# HDMI-OUT.net
KiCad netlist of a schematic drawn in Altium Designer
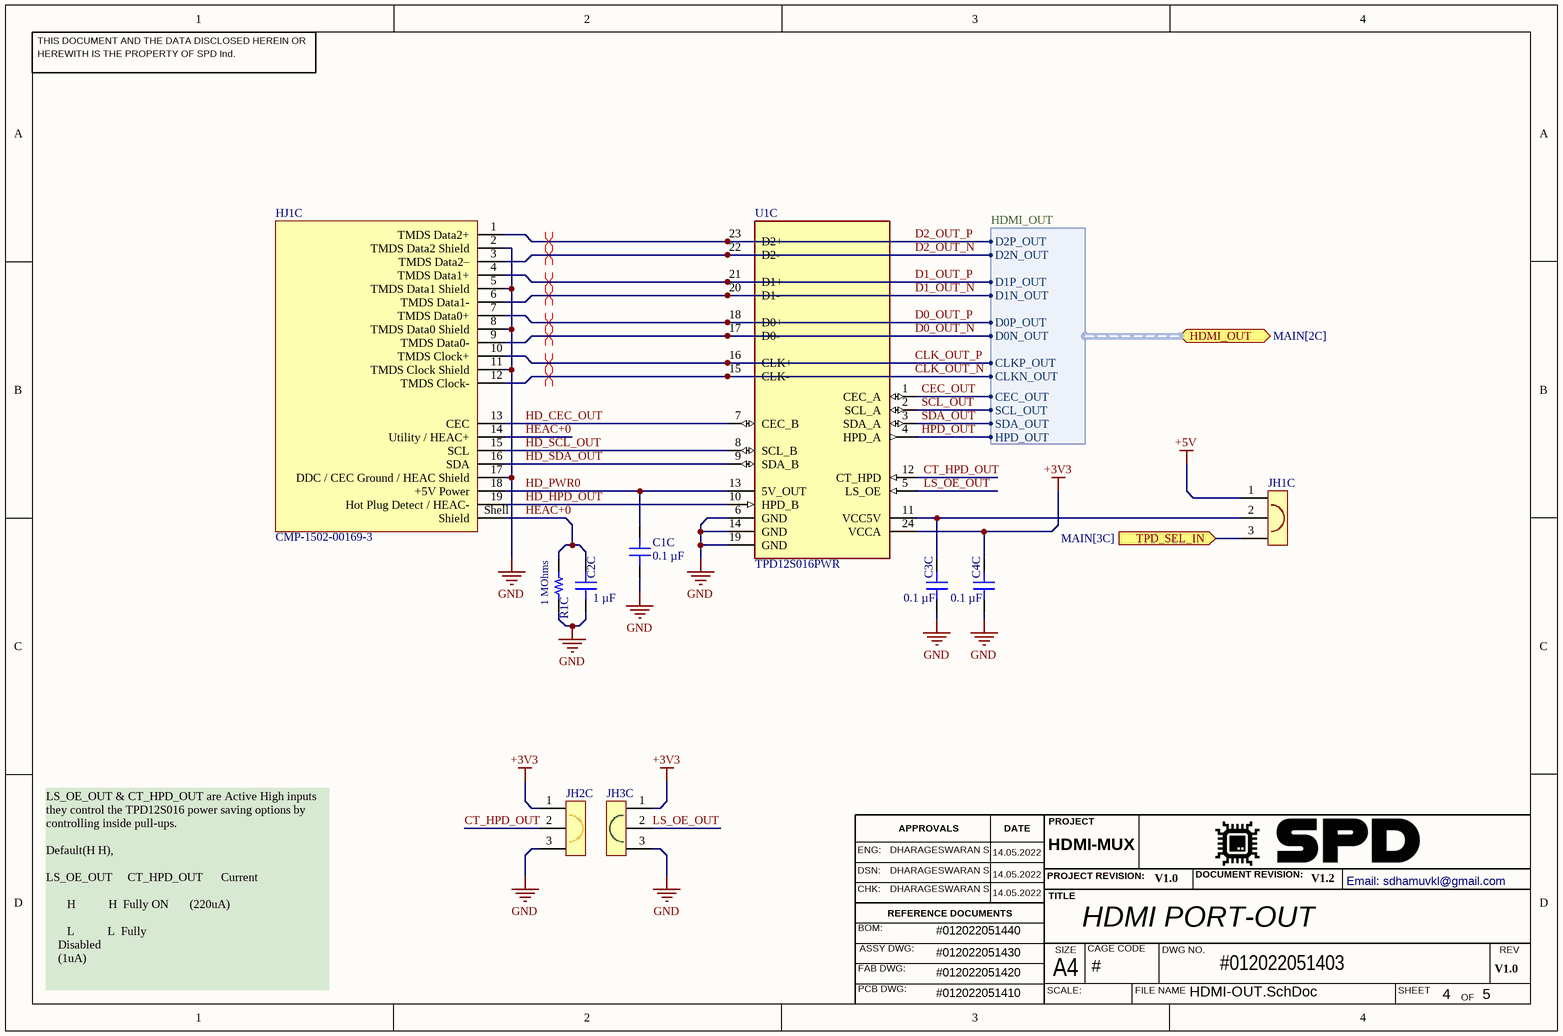
[diagram p0: HDMI-OUT.SchDoc]

(export (version "E")
  (design (tool "Eeschema 10.0.6"))
  (components
    (comp (ref "C1C")
      (value "0.1 µF")
      (footprint "CAP 0603_1608")
      (description "CAP CER 0.1UF 10V X7R 0603")
      (fields (field (name "PART NUMBER") "CC0603KRX7R6BB104") (field (name "MANUFACTURER") "Yageo"))
      (libsource (lib "Postgres Altium Library - altium_library") (part "Capacitor"))
    )
    (comp (ref "C2C")
      (value "1 µF")
      (footprint "CAP 0603_1608")
      (description "CAP CER 1UF 10V Y5V 0603")
      (fields (field (name "PART NUMBER") "CC0603ZRY5V6BB105") (field (name "MANUFACTURER") "Yageo"))
      (libsource (lib "Postgres Altium Library - altium_library") (part "Capacitor"))
    )
    (comp (ref "C3C")
      (value "0.1 µF")
      (footprint "CAP 0603_1608")
      (description "CAP CER 0.1UF 10V X7R 0603")
      (fields (field (name "PART NUMBER") "CC0603KRX7R6BB104") (field (name "MANUFACTURER") "Yageo"))
      (libsource (lib "Postgres Altium Library - altium_library") (part "Capacitor"))
    )
    (comp (ref "C4C")
      (value "0.1 µF")
      (footprint "CAP 0603_1608")
      (description "CAP CER 0.1UF 10V X7R 0603")
      (fields (field (name "PART NUMBER") "CC0603KRX7R6BB104") (field (name "MANUFACTURER") "Yageo"))
      (libsource (lib "Postgres Altium Library - altium_library") (part "Capacitor"))
    )
    (comp (ref "HJ1C")
      (value "CMP-1502-00169-3")
      (footprint "HDMI")
      (libsource (lib "HDMI") (part "CMP-1502-00169-3"))
    )
    (comp (ref "JH1C")
      (value "3PIN-JUMPER-RED")
      (footprint "JUMPER-3PIN-RED")
      (libsource (lib "Jumper-TH") (part "3PIN-JUMPER-RED"))
    )
    (comp (ref "JH2C")
      (value "3PIN-JUMPER-YELLOW")
      (footprint "JUMPER-3PIN-YELLOW")
      (libsource (lib "Jumper-TH") (part "3PIN-JUMPER-YELLOW"))
    )
    (comp (ref "JH3C")
      (value "3PIN-JUMPER-GREEN")
      (footprint "JUMPER-3PIN-GREEN")
      (libsource (lib "Jumper-TH") (part "3PIN-JUMPER-GREEN"))
    )
    (comp (ref "R1C")
      (value "1 MOhms")
      (footprint "RES 0603_1608")
      (description "RES 1 M OHM 5% 1/10W 0603 SMD")
      (fields (field (name "PART NUMBER") "ERJ-U03J105V") (field (name "TOLERANCE") "±5%"))
      (libsource (lib "Postgres Altium Library - altium_library") (part "Resistor"))
    )
    (comp (ref "U1C")
      (value "TPD12S016PWR")
      (footprint "PW0024A_N")
      (fields (field (name "MANUFACTURER") "Texas Instruments"))
      (libsource (lib "TPD12S016PWR") (part "CMP-0326-00070-3"))
    )
  )
  (nets
    (net (code "2") (name "+3V3") (class "Default")
      (node (ref "C4C") (pin "2") (pinfunction "2_2") (pintype "passive"))
      (node (ref "JH2C") (pin "1") (pinfunction "1_1") (pintype "passive"))
      (node (ref "JH3C") (pin "1") (pinfunction "1_1") (pintype "passive"))
      (node (ref "U1C") (pin "24") (pinfunction "VCCA_24") (pintype "power_in"))
    )
    (net (code "3") (name "+5V") (class "Default")
      (node (ref "JH1C") (pin "1") (pinfunction "1_1") (pintype "passive"))
    )
    (net (code "4") (name "/CEC_OUT") (class "Default")
      (node (ref "U1C") (pin "1") (pinfunction "CEC_A_1") (pintype "bidirectional"))
    )
    (net (code "5") (name "/CLK_OUT_N") (class "Default")
      (node (ref "HJ1C") (pin "12") (pinfunction "TMDS_Clock-_12") (pintype "passive"))
      (node (ref "U1C") (pin "15") (pinfunction "CLK-_15") (pintype "passive"))
    )
    (net (code "6") (name "/CLK_OUT_P") (class "Default")
      (node (ref "HJ1C") (pin "10") (pinfunction "TMDS_Clock+_10") (pintype "passive"))
      (node (ref "U1C") (pin "16") (pinfunction "CLK+_16") (pintype "passive"))
    )
    (net (code "7") (name "/CT_HPD_OUT") (class "Default")
      (node (ref "JH2C") (pin "2") (pinfunction "2_2") (pintype "passive"))
      (node (ref "U1C") (pin "12") (pinfunction "CT_HPD_12") (pintype "input"))
    )
    (net (code "8") (name "/D0_OUT_N") (class "Default")
      (node (ref "HJ1C") (pin "9") (pinfunction "TMDS_Data0-_9") (pintype "passive"))
      (node (ref "U1C") (pin "17") (pinfunction "D0-_17") (pintype "passive"))
    )
    (net (code "9") (name "/D0_OUT_P") (class "Default")
      (node (ref "HJ1C") (pin "7") (pinfunction "TMDS_Data0+_7") (pintype "passive"))
      (node (ref "U1C") (pin "18") (pinfunction "D0+_18") (pintype "passive"))
    )
    (net (code "10") (name "/D1_OUT_N") (class "Default")
      (node (ref "HJ1C") (pin "6") (pinfunction "TMDS_Data1-_6") (pintype "passive"))
      (node (ref "U1C") (pin "20") (pinfunction "D1-_20") (pintype "passive"))
    )
    (net (code "11") (name "/D1_OUT_P") (class "Default")
      (node (ref "HJ1C") (pin "4") (pinfunction "TMDS_Data1+_4") (pintype "passive"))
      (node (ref "U1C") (pin "21") (pinfunction "D1+_21") (pintype "passive"))
    )
    (net (code "12") (name "/D2_OUT_N") (class "Default")
      (node (ref "HJ1C") (pin "3") (pinfunction "TMDS_Data2–_3") (pintype "passive"))
      (node (ref "U1C") (pin "22") (pinfunction "D2-_22") (pintype "passive"))
    )
    (net (code "13") (name "/D2_OUT_P") (class "Default")
      (node (ref "HJ1C") (pin "1") (pinfunction "TMDS_Data2+_1") (pintype "passive"))
      (node (ref "U1C") (pin "23") (pinfunction "D2+_23") (pintype "passive"))
    )
    (net (code "14") (name "/HD_CEC_OUT") (class "Default")
      (node (ref "HJ1C") (pin "13") (pinfunction "CEC_13") (pintype "passive"))
      (node (ref "U1C") (pin "7") (pinfunction "CEC_B_7") (pintype "bidirectional"))
    )
    (net (code "15") (name "/HD_HPD_OUT") (class "Default")
      (node (ref "HJ1C") (pin "19") (pinfunction "Hot_Plug_Detect_/_HEAC-_19") (pintype "passive"))
      (node (ref "U1C") (pin "10") (pinfunction "HPD_B_10") (pintype "input"))
    )
    (net (code "16") (name "/HD_PWR0") (class "Default")
      (node (ref "C1C") (pin "2") (pinfunction "2_2") (pintype "passive"))
      (node (ref "HJ1C") (pin "18") (pinfunction "+5V_Power_18") (pintype "passive"))
      (node (ref "U1C") (pin "13") (pinfunction "5V_OUT_13") (pintype "power_in"))
    )
    (net (code "17") (name "/HD_SCL_OUT") (class "Default")
      (node (ref "HJ1C") (pin "15") (pinfunction "SCL_15") (pintype "passive"))
      (node (ref "U1C") (pin "8") (pinfunction "SCL_B_8") (pintype "bidirectional"))
    )
    (net (code "18") (name "/HD_SDA_OUT") (class "Default")
      (node (ref "HJ1C") (pin "16") (pinfunction "SDA_16") (pintype "passive"))
      (node (ref "U1C") (pin "9") (pinfunction "SDA_B_9") (pintype "bidirectional"))
    )
    (net (code "19") (name "/HEAC+0") (class "Default")
      (node (ref "C2C") (pin "2") (pinfunction "2_2") (pintype "passive"))
      (node (ref "HJ1C") (pin "14") (pinfunction "Utility_/_HEAC+_14") (pintype "passive"))
      (node (ref "HJ1C") (pin "Shell") (pinfunction "Shield_Shell") (pintype "passive"))
      (node (ref "R1C") (pin "2") (pinfunction "2_2") (pintype "passive"))
    )
    (net (code "20") (name "/HPD_OUT") (class "Default")
      (node (ref "U1C") (pin "4") (pinfunction "HPD_A_4") (pintype "output"))
    )
    (net (code "21") (name "/LS_OE_OUT") (class "Default")
      (node (ref "JH3C") (pin "2") (pinfunction "2_2") (pintype "passive"))
      (node (ref "U1C") (pin "5") (pinfunction "LS_OE_5") (pintype "input"))
    )
    (net (code "22") (name "/SCL_OUT") (class "Default")
      (node (ref "U1C") (pin "2") (pinfunction "SCL_A_2") (pintype "bidirectional"))
    )
    (net (code "23") (name "/SDA_OUT") (class "Default")
      (node (ref "U1C") (pin "3") (pinfunction "SDA_A_3") (pintype "bidirectional"))
    )
    (net (code "24") (name "/TPD_SEL_IN") (class "Default")
      (node (ref "JH1C") (pin "3") (pinfunction "3_3") (pintype "passive"))
    )
    (net (code "26") (name "GND") (class "Default")
      (node (ref "C1C") (pin "1") (pinfunction "1_1") (pintype "passive"))
      (node (ref "C2C") (pin "1") (pinfunction "1_1") (pintype "passive"))
      (node (ref "C3C") (pin "1") (pinfunction "1_1") (pintype "passive"))
      (node (ref "C4C") (pin "1") (pinfunction "1_1") (pintype "passive"))
      (node (ref "HJ1C") (pin "11") (pinfunction "TMDS_Clock_Shield_11") (pintype "passive"))
      (node (ref "HJ1C") (pin "17") (pinfunction "DDC_/_CEC_Ground_/_HEAC_Shield_17") (pintype "passive"))
      (node (ref "HJ1C") (pin "2") (pinfunction "TMDS_Data2_Shield_2") (pintype "passive"))
      (node (ref "HJ1C") (pin "5") (pinfunction "TMDS_Data1_Shield_5") (pintype "passive"))
      (node (ref "HJ1C") (pin "8") (pinfunction "TMDS_Data0_Shield_8") (pintype "passive"))
      (node (ref "JH2C") (pin "3") (pinfunction "3_3") (pintype "passive"))
      (node (ref "JH3C") (pin "3") (pinfunction "3_3") (pintype "passive"))
      (node (ref "R1C") (pin "1") (pinfunction "1_1") (pintype "passive"))
      (node (ref "U1C") (pin "14") (pinfunction "GND_14") (pintype "power_in"))
      (node (ref "U1C") (pin "19") (pinfunction "GND_19") (pintype "power_in"))
      (node (ref "U1C") (pin "6") (pinfunction "GND_6") (pintype "power_in"))
    )
    (net (code "27") (name "Net-(U1C-VCC5V)") (class "Default")
      (node (ref "C3C") (pin "2") (pinfunction "2_2") (pintype "passive"))
      (node (ref "JH1C") (pin "2") (pinfunction "2_2") (pintype "passive"))
      (node (ref "U1C") (pin "11") (pinfunction "VCC5V_11") (pintype "power_in"))
    )
  )
)
